# Bessel.net
KiCad netlist of a schematic drawn in Altium Designer
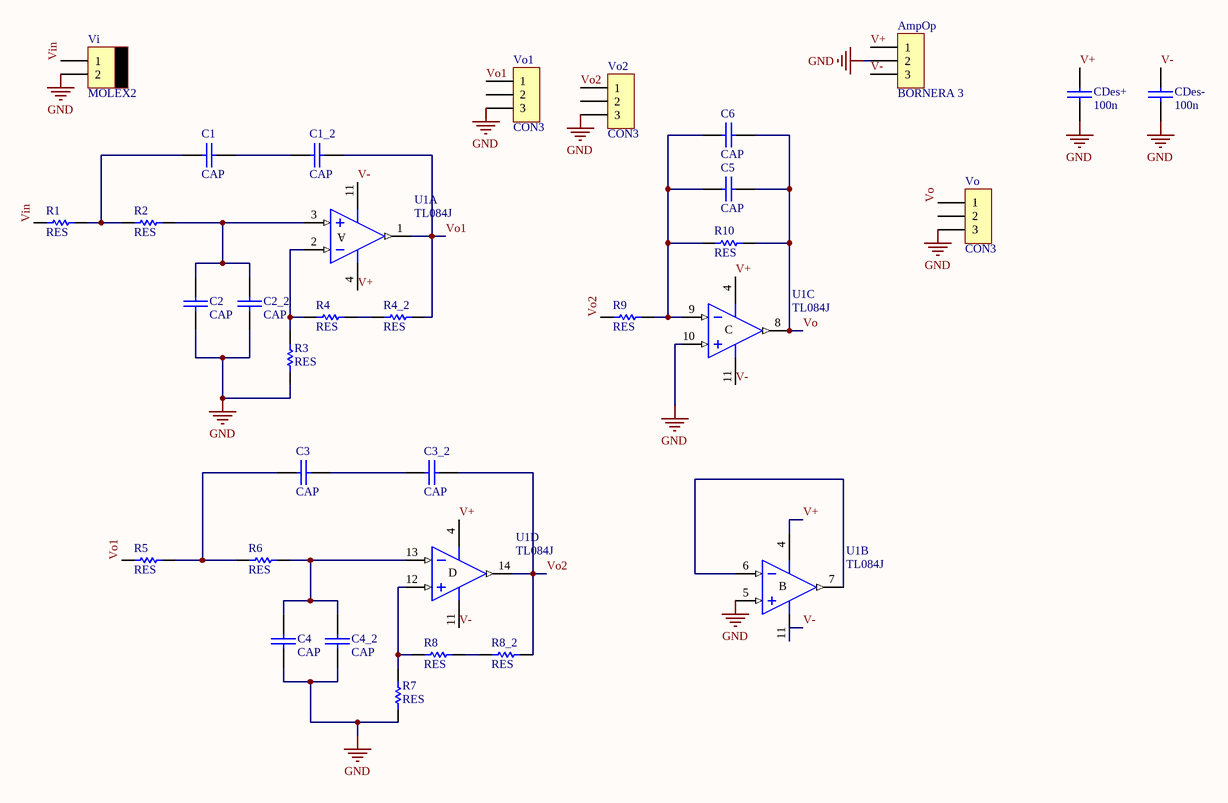
[diagram p0: Bessel.SchDoc]

(export (version "E")
  (design (tool "Eeschema 10.0.6"))
  (components
    (comp (ref "AmpOp")
      (value "BORNERA 3")
      (footprint "BORNERA3")
      (libsource (lib "LIBEBAL") (part "BORNERA 3"))
    )
    (comp (ref "C1") (value "CAP") (footprint "CAP200") (libsource (lib "LIBEBAL") (part "CAP")))
    (comp (ref "C1_2") (value "CAP") (footprint "CAP200") (libsource (lib "LIBEBAL") (part "CAP")))
    (comp (ref "C2") (value "CAP") (footprint "CAP200") (libsource (lib "LIBEBAL") (part "CAP")))
    (comp (ref "C2_2") (value "CAP") (footprint "CAP200") (libsource (lib "LIBEBAL") (part "CAP")))
    (comp (ref "C3") (value "CAP") (footprint "CAP200") (libsource (lib "LIBEBAL") (part "CAP")))
    (comp (ref "C3_2") (value "CAP") (footprint "0805") (libsource (lib "LIBEBAL") (part "CAP")))
    (comp (ref "C4") (value "CAP") (footprint "CAP200") (libsource (lib "LIBEBAL") (part "CAP")))
    (comp (ref "C4_2") (value "CAP") (footprint "CAP200") (libsource (lib "LIBEBAL") (part "CAP")))
    (comp (ref "C5") (value "CAP") (footprint "CAP200") (libsource (lib "LIBEBAL") (part "CAP")))
    (comp (ref "C6") (value "CAP") (footprint "CAP200") (libsource (lib "LIBEBAL") (part "CAP")))
    (comp (ref "CDes+") (value "100n") (footprint "CAP200") (libsource (lib "LIBEBAL") (part "CAP")))
    (comp (ref "CDes-") (value "100n") (footprint "CAP200") (libsource (lib "LIBEBAL") (part "CAP")))
    (comp (ref "R1") (value "RES") (footprint "RES400") (libsource (lib "LIBEBAL") (part "RES")))
    (comp (ref "R2") (value "RES") (footprint "RES400") (libsource (lib "LIBEBAL") (part "RES")))
    (comp (ref "R3") (value "RES") (footprint "0805") (libsource (lib "LIBEBAL") (part "RES")))
    (comp (ref "R4") (value "RES") (footprint "0805") (libsource (lib "LIBEBAL") (part "RES")))
    (comp (ref "R4_2") (value "RES") (footprint "0805") (libsource (lib "LIBEBAL") (part "RES")))
    (comp (ref "R5") (value "RES") (footprint "RES400") (libsource (lib "LIBEBAL") (part "RES")))
    (comp (ref "R6") (value "RES") (footprint "RES400") (libsource (lib "LIBEBAL") (part "RES")))
    (comp (ref "R7") (value "RES") (footprint "0805") (libsource (lib "LIBEBAL") (part "RES")))
    (comp (ref "R8") (value "RES") (footprint "0805") (libsource (lib "LIBEBAL") (part "RES")))
    (comp (ref "R8_2") (value "RES") (footprint "0805") (libsource (lib "LIBEBAL") (part "RES")))
    (comp (ref "R9") (value "RES") (footprint "RES400") (libsource (lib "LIBEBAL") (part "RES")))
    (comp (ref "R10") (value "RES") (footprint "RES400") (libsource (lib "LIBEBAL") (part "RES")))
    (comp (ref "U1")
      (value "TL084J")
      (footprint "J014")
      (description "JFET-Input Operational Amplifier")
      (fields (field (name "PUBLISHER") "Altium Limited"))
      (libsource (lib "TI Operational Amplifier") (part "TL084J"))
    )
    (comp (ref "Vi") (value "MOLEX2") (footprint "MOLEX2") (libsource (lib "LIBEBAL") (part "MOLEX2")))
    (comp (ref "Vo") (value "CON3") (footprint "SIP3") (libsource (lib "LIBEBAL") (part "CON3")))
    (comp (ref "Vo1") (value "CON3") (footprint "SIP3") (libsource (lib "LIBEBAL") (part "CON3")))
    (comp (ref "Vo2") (value "CON3") (footprint "SIP3") (libsource (lib "LIBEBAL") (part "CON3")))
  )
  (nets
    (net (code "1") (name "/V+") (class "Default")
      (node (ref "AmpOp") (pin "1") (pinfunction "1_1") (pintype "passive"))
      (node (ref "CDes+") (pin "1") (pinfunction "1_1") (pintype "passive"))
      (node (ref "U1") (pin "4") (pinfunction "V+_4") (pintype "power_in"))
    )
    (net (code "2") (name "/V-") (class "Default")
      (node (ref "AmpOp") (pin "3") (pinfunction "3_3") (pintype "passive"))
      (node (ref "CDes-") (pin "1") (pinfunction "1_1") (pintype "passive"))
      (node (ref "U1") (pin "11") (pinfunction "V-_11") (pintype "power_in"))
    )
    (net (code "3") (name "/Vin") (class "Default")
      (node (ref "R1") (pin "1") (pinfunction "1_1") (pintype "passive"))
      (node (ref "Vi") (pin "1") (pinfunction "1_1") (pintype "passive"))
    )
    (net (code "4") (name "/Vo") (class "Default")
      (node (ref "C5") (pin "2") (pinfunction "2_2") (pintype "passive"))
      (node (ref "C6") (pin "2") (pinfunction "2_2") (pintype "passive"))
      (node (ref "R10") (pin "2") (pinfunction "2_2") (pintype "passive"))
      (node (ref "U1") (pin "8") (pinfunction "OUT_8") (pintype "output"))
      (node (ref "Vo") (pin "1") (pinfunction "1_1") (pintype "passive"))
    )
    (net (code "5") (name "/Vo1") (class "Default")
      (node (ref "C1_2") (pin "2") (pinfunction "2_2") (pintype "passive"))
      (node (ref "R4_2") (pin "1") (pinfunction "1_1") (pintype "passive"))
      (node (ref "R5") (pin "1") (pinfunction "1_1") (pintype "passive"))
      (node (ref "U1") (pin "1") (pinfunction "OUT_1") (pintype "output"))
      (node (ref "Vo1") (pin "1") (pinfunction "1_1") (pintype "passive"))
    )
    (net (code "6") (name "/Vo2") (class "Default")
      (node (ref "C3_2") (pin "2") (pinfunction "2_2") (pintype "passive"))
      (node (ref "R8_2") (pin "2") (pinfunction "2_2") (pintype "passive"))
      (node (ref "R9") (pin "1") (pinfunction "1_1") (pintype "passive"))
      (node (ref "U1") (pin "14") (pinfunction "OUT_14") (pintype "output"))
      (node (ref "Vo2") (pin "1") (pinfunction "1_1") (pintype "passive"))
    )
    (net (code "7") (name "GND") (class "Default")
      (node (ref "AmpOp") (pin "2") (pinfunction "2_2") (pintype "passive"))
      (node (ref "C2") (pin "2") (pinfunction "2_2") (pintype "passive"))
      (node (ref "C2_2") (pin "2") (pinfunction "2_2") (pintype "passive"))
      (node (ref "C4") (pin "2") (pinfunction "2_2") (pintype "passive"))
      (node (ref "C4_2") (pin "2") (pinfunction "2_2") (pintype "passive"))
      (node (ref "CDes+") (pin "2") (pinfunction "2_2") (pintype "passive"))
      (node (ref "CDes-") (pin "2") (pinfunction "2_2") (pintype "passive"))
      (node (ref "R3") (pin "1") (pinfunction "1_1") (pintype "passive"))
      (node (ref "R7") (pin "1") (pinfunction "1_1") (pintype "passive"))
      (node (ref "U1") (pin "10") (pinfunction "IN+_10") (pintype "input"))
      (node (ref "U1") (pin "5") (pinfunction "IN+_5") (pintype "input"))
      (node (ref "Vi") (pin "2") (pinfunction "2_2") (pintype "passive"))
      (node (ref "Vo") (pin "3") (pinfunction "3_3") (pintype "passive"))
      (node (ref "Vo1") (pin "3") (pinfunction "3_3") (pintype "passive"))
      (node (ref "Vo2") (pin "3") (pinfunction "3_3") (pintype "passive"))
    )
    (net (code "8") (name "Net-(C1-Pad1)") (class "Default")
      (node (ref "C1") (pin "1") (pinfunction "1_1") (pintype "passive"))
      (node (ref "R1") (pin "2") (pinfunction "2_2") (pintype "passive"))
      (node (ref "R2") (pin "1") (pinfunction "1_1") (pintype "passive"))
    )
    (net (code "9") (name "Net-(C1-Pad2)") (class "Default")
      (node (ref "C1") (pin "2") (pinfunction "2_2") (pintype "passive"))
      (node (ref "C1_2") (pin "1") (pinfunction "1_1") (pintype "passive"))
    )
    (net (code "10") (name "Net-(C3-Pad1)") (class "Default")
      (node (ref "C3") (pin "1") (pinfunction "1_1") (pintype "passive"))
      (node (ref "R5") (pin "2") (pinfunction "2_2") (pintype "passive"))
      (node (ref "R6") (pin "1") (pinfunction "1_1") (pintype "passive"))
    )
    (net (code "11") (name "Net-(C3-Pad2)") (class "Default")
      (node (ref "C3") (pin "2") (pinfunction "2_2") (pintype "passive"))
      (node (ref "C3_2") (pin "1") (pinfunction "1_1") (pintype "passive"))
    )
    (net (code "12") (name "Net-(R4-Pad2)") (class "Default")
      (node (ref "R4") (pin "2") (pinfunction "2_2") (pintype "passive"))
      (node (ref "R4_2") (pin "2") (pinfunction "2_2") (pintype "passive"))
    )
    (net (code "13") (name "Net-(R8-Pad2)") (class "Default")
      (node (ref "R8") (pin "2") (pinfunction "2_2") (pintype "passive"))
      (node (ref "R8_2") (pin "1") (pinfunction "1_1") (pintype "passive"))
    )
    (net (code "14") (name "Net-(U1A-IN+)") (class "Default")
      (node (ref "C2") (pin "1") (pinfunction "1_1") (pintype "passive"))
      (node (ref "C2_2") (pin "1") (pinfunction "1_1") (pintype "passive"))
      (node (ref "R2") (pin "2") (pinfunction "2_2") (pintype "passive"))
      (node (ref "U1") (pin "3") (pinfunction "IN+_3") (pintype "input"))
    )
    (net (code "15") (name "Net-(U1A-IN-)") (class "Default")
      (node (ref "R3") (pin "2") (pinfunction "2_2") (pintype "passive"))
      (node (ref "R4") (pin "1") (pinfunction "1_1") (pintype "passive"))
      (node (ref "U1") (pin "2") (pinfunction "IN-_2") (pintype "input"))
    )
    (net (code "16") (name "Net-(U1B-IN-)") (class "Default")
      (node (ref "U1") (pin "6") (pinfunction "IN-_6") (pintype "input"))
      (node (ref "U1") (pin "7") (pinfunction "OUT_7") (pintype "output"))
    )
    (net (code "17") (name "Net-(U1C-IN-)") (class "Default")
      (node (ref "C5") (pin "1") (pinfunction "1_1") (pintype "passive"))
      (node (ref "C6") (pin "1") (pinfunction "1_1") (pintype "passive"))
      (node (ref "R10") (pin "1") (pinfunction "1_1") (pintype "passive"))
      (node (ref "R9") (pin "2") (pinfunction "2_2") (pintype "passive"))
      (node (ref "U1") (pin "9") (pinfunction "IN-_9") (pintype "input"))
    )
    (net (code "18") (name "Net-(U1D-IN+)") (class "Default")
      (node (ref "R7") (pin "2") (pinfunction "2_2") (pintype "passive"))
      (node (ref "R8") (pin "1") (pinfunction "1_1") (pintype "passive"))
      (node (ref "U1") (pin "12") (pinfunction "IN+_12") (pintype "input"))
    )
    (net (code "19") (name "Net-(U1D-IN-)") (class "Default")
      (node (ref "C4") (pin "1") (pinfunction "1_1") (pintype "passive"))
      (node (ref "C4_2") (pin "1") (pinfunction "1_1") (pintype "passive"))
      (node (ref "R6") (pin "2") (pinfunction "2_2") (pintype "passive"))
      (node (ref "U1") (pin "13") (pinfunction "IN-_13") (pintype "input"))
    )
    (net (code "20") (name "unconnected-(Vo-Pad2)") (class "Default")
      (node (ref "Vo") (pin "2") (pinfunction "2_2") (pintype "passive"))
    )
    (net (code "21") (name "unconnected-(Vo1-Pad2)") (class "Default")
      (node (ref "Vo1") (pin "2") (pinfunction "2_2") (pintype "passive"))
    )
    (net (code "22") (name "unconnected-(Vo2-Pad2)") (class "Default")
      (node (ref "Vo2") (pin "2") (pinfunction "2_2") (pintype "passive"))
    )
  )
)
